# SenseLoRa_Industrial-grade_Air_Monitor_V.net
KiCad netlist of a schematic drawn in EAGLE
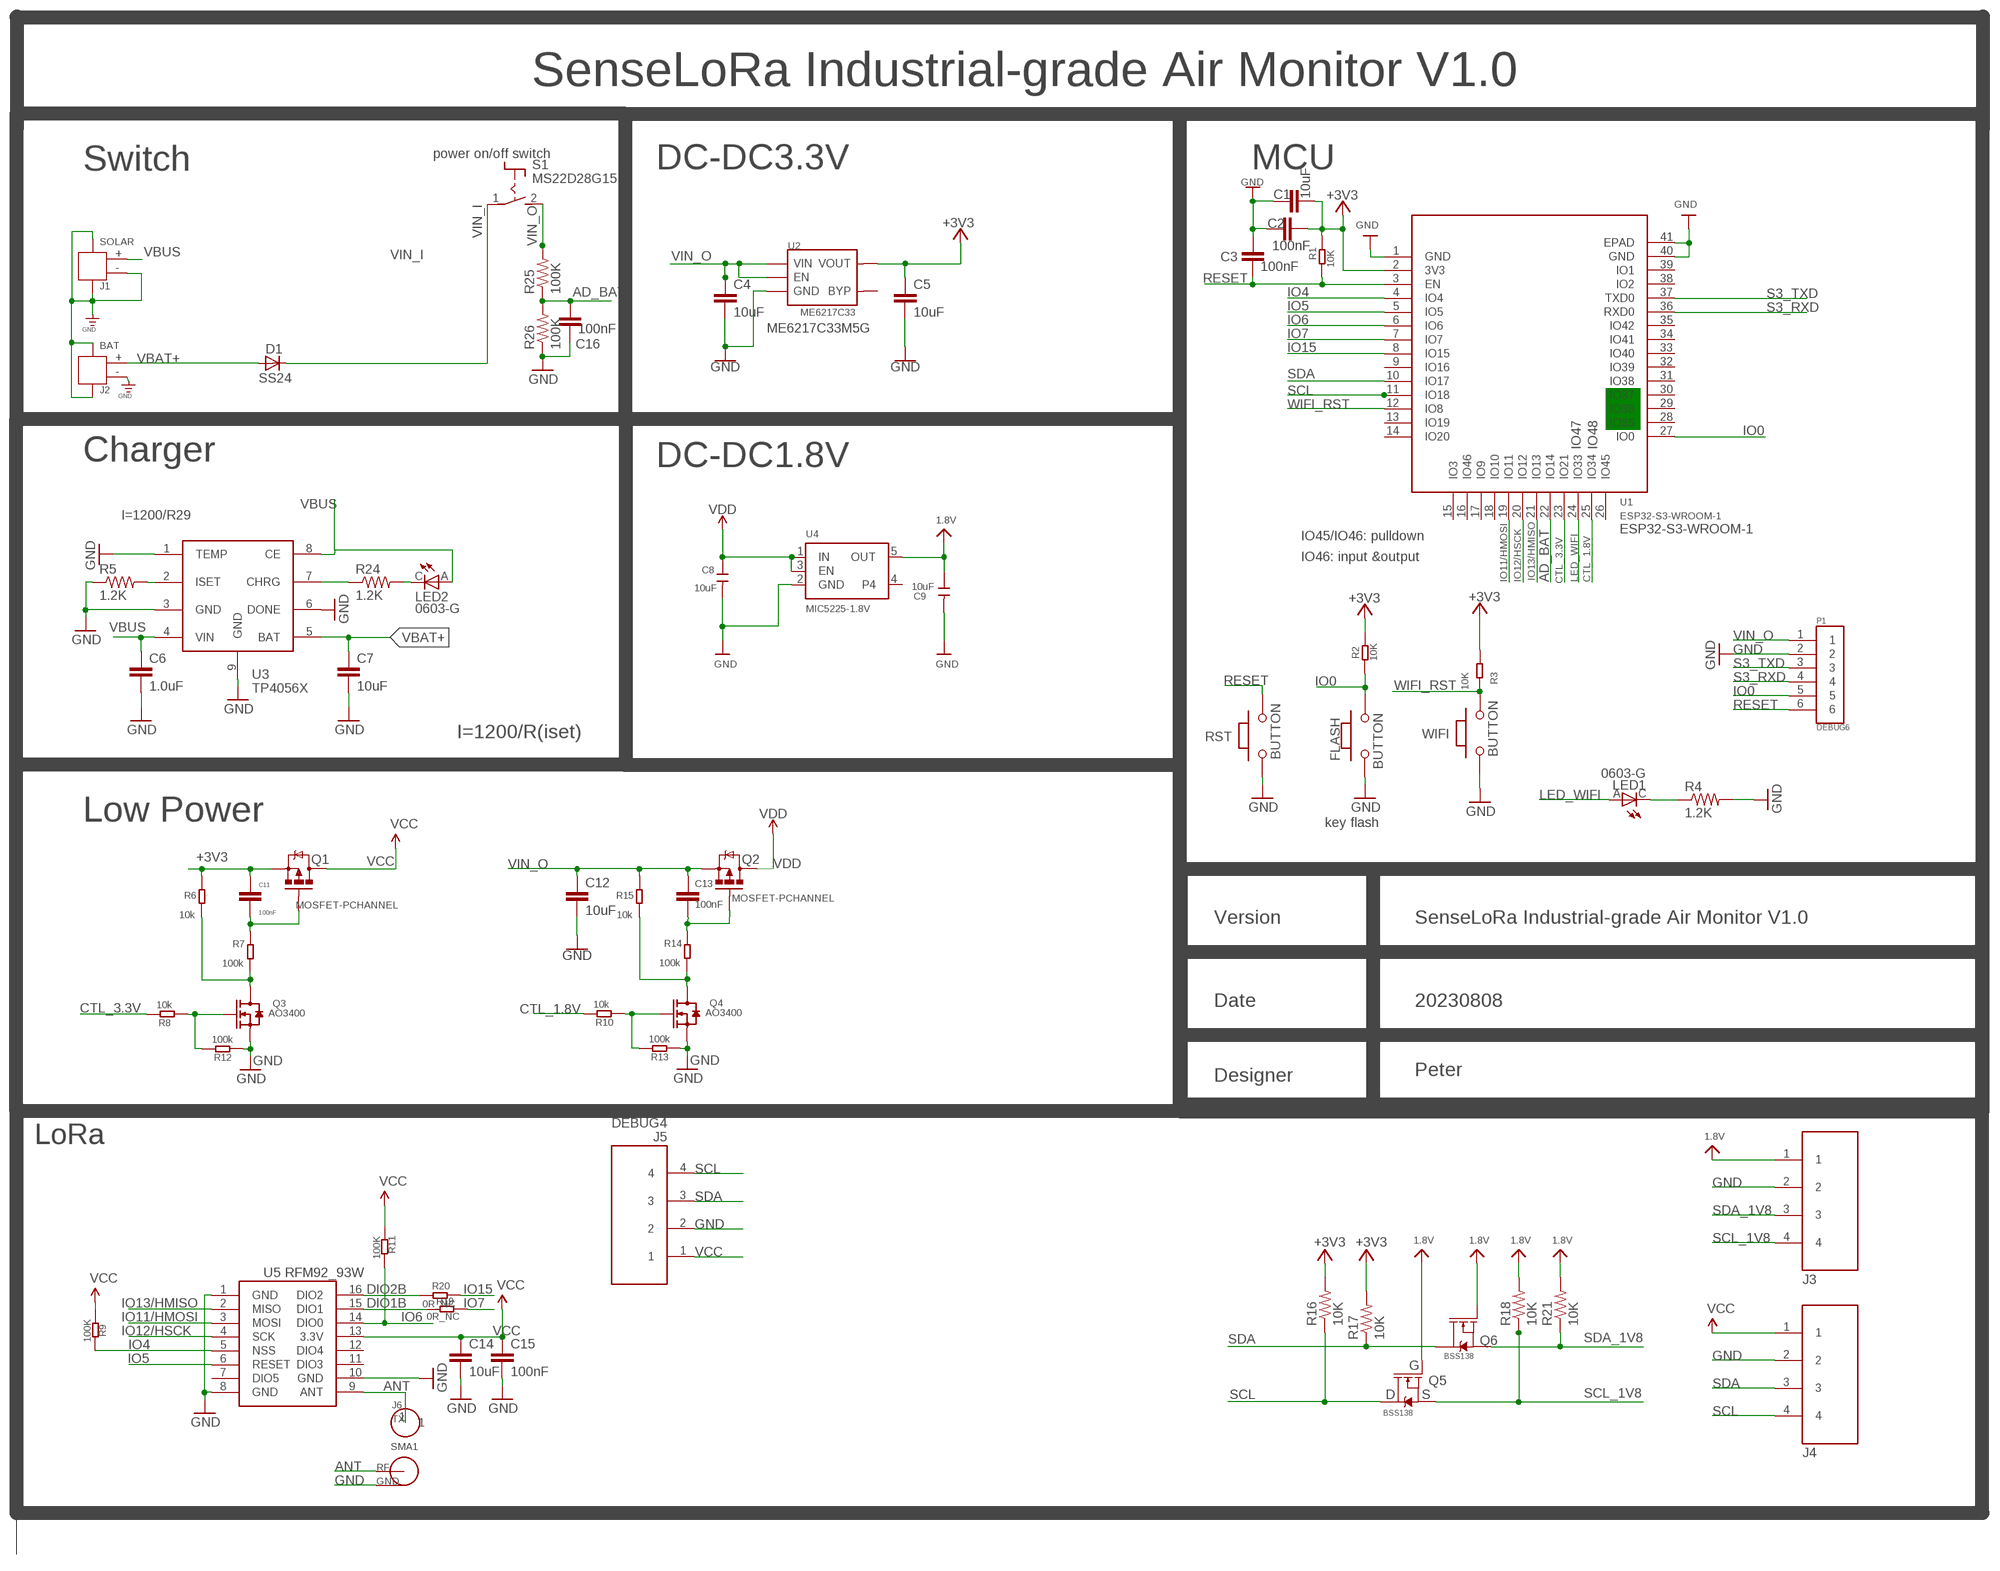
[diagram p0: schematic, sheet 1]

(export (version "E")
  (design (tool "Eeschema 10.0.6"))
  (components
    (comp (ref "C1")
      (value "10uF")
      (footprint "eagle-import:C0603")
      (libsource (lib "eagle-import") (part "C0603"))
    )
    (comp (ref "C2")
      (value "100nF")
      (footprint "eagle-import:C0603")
      (libsource (lib "eagle-import") (part "C0603"))
    )
    (comp (ref "C3")
      (value "100nF")
      (footprint "eagle-import:C0603")
      (libsource (lib "eagle-import") (part "C0603"))
    )
    (comp (ref "C4")
      (value "10uF")
      (footprint "eagle-import:C0603")
      (libsource (lib "eagle-import") (part "C0603"))
    )
    (comp (ref "C5")
      (value "10uF")
      (footprint "eagle-import:C0603")
      (libsource (lib "eagle-import") (part "C0603"))
    )
    (comp (ref "C6")
      (value "1.0uF")
      (footprint "eagle-import:C0603")
      (libsource (lib "eagle-import") (part "C0603"))
    )
    (comp (ref "C7")
      (value "10uF")
      (footprint "eagle-import:C0603")
      (libsource (lib "eagle-import") (part "C0603"))
    )
    (comp (ref "C8")
      (value "10uF")
      (footprint "eagle-import:0603")
      (libsource (lib "eagle-import") (part "C-0603"))
    )
    (comp (ref "C9")
      (value "10uF")
      (footprint "eagle-import:0603")
      (libsource (lib "eagle-import") (part "C-0603"))
    )
    (comp (ref "C11")
      (value "100nF")
      (footprint "eagle-import:C0603")
      (libsource (lib "eagle-import") (part "C0603"))
    )
    (comp (ref "C12")
      (value "10uF")
      (footprint "eagle-import:C0603")
      (libsource (lib "eagle-import") (part "C0603"))
    )
    (comp (ref "C13")
      (value "100nF")
      (footprint "eagle-import:C0603")
      (libsource (lib "eagle-import") (part "C0603"))
    )
    (comp (ref "C14")
      (value "10uF")
      (footprint "eagle-import:C0603")
      (libsource (lib "eagle-import") (part "C0603"))
    )
    (comp (ref "C15")
      (value "100nF")
      (footprint "eagle-import:C0603")
      (libsource (lib "eagle-import") (part "C0603"))
    )
    (comp (ref "C16")
      (value "100nF")
      (footprint "eagle-import:C0603")
      (libsource (lib "eagle-import") (part "C0603"))
    )
    (comp (ref "D1")
      (value "SS24")
      (footprint "eagle-import:DO-214AC")
      (libsource (lib "eagle-import") (part "DIODE-DO-214AC"))
    )
    (comp (ref "FLASH")
      (value "BUTTON")
      (footprint "eagle-import:157SW")
      (libsource (lib "eagle-import") (part "PB157"))
    )
    (comp (ref "J1")
      (value "SOLAR")
      (footprint "eagle-import:HW2-SMD-2.0-90D")
      (libsource (lib "eagle-import") (part "JST-2P-SMD'2.0'"))
    )
    (comp (ref "J2")
      (value "BAT")
      (footprint "eagle-import:HW2-SMD-2.0-90D")
      (libsource (lib "eagle-import") (part "JST-2P-SMD'2.0'"))
    )
    (comp (ref "J3")
      (value "CONNNECT-SMD-1.25X4P")
      (footprint "eagle-import:CONNNECT-SMD-1.25X4P")
      (libsource (lib "eagle-import") (part "CONNNECT-SMD-1.25X4P"))
    )
    (comp (ref "J4")
      (value "CONNNECT-SMD-1.25X4P")
      (footprint "eagle-import:CONNNECT-SMD-1.25X4P")
      (libsource (lib "eagle-import") (part "CONNNECT-SMD-1.25X4P"))
    )
    (comp (ref "J5")
      (value "DEBUG4")
      (footprint "eagle-import:DEBUG_4")
      (libsource (lib "eagle-import") (part "DEBUG4"))
    )
    (comp (ref "J6")
      (value "TX")
      (footprint "eagle-import:1P-100_50MIL")
      (libsource (lib "eagle-import") (part "HEADER-1P-50"))
    )
    (comp (ref "LED1")
      (value "0603-G")
      (footprint "eagle-import:LED0603")
      (libsource (lib "eagle-import") (part "LED0603"))
    )
    (comp (ref "LED2")
      (value "0603-G")
      (footprint "eagle-import:LED0603")
      (libsource (lib "eagle-import") (part "LED0603"))
    )
    (comp (ref "P1")
      (value "DEBUG6")
      (footprint "eagle-import:DEBUG_6")
      (libsource (lib "eagle-import") (part "DEBUG6"))
    )
    (comp (ref "Q1")
      (value "MOSFET-PCHANNEL")
      (footprint "eagle-import:SOT23-3")
      (fields (field (name "PROD_ID") "TRANS-08285"))
      (libsource (lib "eagle-import") (part "MOSFET-PCHANNEL"))
    )
    (comp (ref "Q2")
      (value "MOSFET-PCHANNEL")
      (footprint "eagle-import:SOT23-3")
      (fields (field (name "PROD_ID") "TRANS-08285"))
      (libsource (lib "eagle-import") (part "MOSFET-PCHANNEL"))
    )
    (comp (ref "Q3")
      (value "AO3400")
      (footprint "eagle-import:SOT23@1")
      (libsource (lib "eagle-import") (part "MOSFET-N'SOT23'"))
    )
    (comp (ref "Q4")
      (value "AO3400")
      (footprint "eagle-import:SOT23@1")
      (libsource (lib "eagle-import") (part "MOSFET-N'SOT23'"))
    )
    (comp (ref "Q5")
      (value "BSS138")
      (footprint "eagle-import:SOT23-3")
      (libsource (lib "eagle-import") (part "MOSFET-NCH-BSS138"))
    )
    (comp (ref "Q6")
      (value "BSS138")
      (footprint "eagle-import:SOT23-3")
      (fields (field (name "PROD_ID") "TRANS-00830"))
      (libsource (lib "eagle-import") (part "MOSFET-NCH-BSS138"))
    )
    (comp (ref "R1")
      (value "10K")
      (footprint "eagle-import:R0603")
      (libsource (lib "eagle-import") (part "R-0603"))
    )
    (comp (ref "R2")
      (value "10K")
      (footprint "eagle-import:R0603")
      (libsource (lib "eagle-import") (part "R-0603"))
    )
    (comp (ref "R3")
      (value "10K")
      (footprint "eagle-import:R0603")
      (libsource (lib "eagle-import") (part "R-0603"))
    )
    (comp (ref "R4")
      (value "1.2K")
      (footprint "eagle-import:R0603")
      (libsource (lib "eagle-import") (part "R0603"))
    )
    (comp (ref "R5")
      (value "1.2K")
      (footprint "eagle-import:R0603")
      (libsource (lib "eagle-import") (part "R0603"))
    )
    (comp (ref "R6")
      (value "10k")
      (footprint "eagle-import:R0603")
      (libsource (lib "eagle-import") (part "R-0603"))
    )
    (comp (ref "R7")
      (value "100k")
      (footprint "eagle-import:R0603")
      (libsource (lib "eagle-import") (part "R-0603"))
    )
    (comp (ref "R8")
      (value "10k")
      (footprint "eagle-import:R0603")
      (libsource (lib "eagle-import") (part "R-0603"))
    )
    (comp (ref "R9")
      (value "100K")
      (footprint "eagle-import:R0603")
      (libsource (lib "eagle-import") (part "R-0603"))
    )
    (comp (ref "R10")
      (value "10k")
      (footprint "eagle-import:R0603")
      (libsource (lib "eagle-import") (part "R-0603"))
    )
    (comp (ref "R11")
      (value "100K")
      (footprint "eagle-import:R0603")
      (libsource (lib "eagle-import") (part "R-0603"))
    )
    (comp (ref "R12")
      (value "100k")
      (footprint "eagle-import:R0603")
      (libsource (lib "eagle-import") (part "R-0603"))
    )
    (comp (ref "R13")
      (value "100k")
      (footprint "eagle-import:R0603")
      (libsource (lib "eagle-import") (part "R-0603"))
    )
    (comp (ref "R14")
      (value "100k")
      (footprint "eagle-import:R0603")
      (libsource (lib "eagle-import") (part "R-0603"))
    )
    (comp (ref "R15")
      (value "10k")
      (footprint "eagle-import:R0603")
      (libsource (lib "eagle-import") (part "R-0603"))
    )
    (comp (ref "R16")
      (value "10K")
      (footprint "eagle-import:R0603")
      (libsource (lib "eagle-import") (part "R0603"))
    )
    (comp (ref "R17")
      (value "10K")
      (footprint "eagle-import:R0603")
      (libsource (lib "eagle-import") (part "R0603"))
    )
    (comp (ref "R18")
      (value "10K")
      (footprint "eagle-import:R0603")
      (libsource (lib "eagle-import") (part "R0603"))
    )
    (comp (ref "R19")
      (value "0R_NC")
      (footprint "eagle-import:R0603")
      (libsource (lib "eagle-import") (part "R-0603"))
    )
    (comp (ref "R20")
      (value "0R_NC")
      (footprint "eagle-import:R0603")
      (libsource (lib "eagle-import") (part "R-0603"))
    )
    (comp (ref "R21")
      (value "10K")
      (footprint "eagle-import:R0603")
      (libsource (lib "eagle-import") (part "R0603"))
    )
    (comp (ref "R24")
      (value "1.2K")
      (footprint "eagle-import:R0603")
      (libsource (lib "eagle-import") (part "R0603"))
    )
    (comp (ref "R25")
      (value "100K")
      (footprint "eagle-import:R0603")
      (libsource (lib "eagle-import") (part "R0603"))
    )
    (comp (ref "R26")
      (value "100K")
      (footprint "eagle-import:R0603")
      (libsource (lib "eagle-import") (part "R0603"))
    )
    (comp (ref "RST")
      (value "BUTTON")
      (footprint "eagle-import:157SW")
      (libsource (lib "eagle-import") (part "PB157"))
    )
    (comp (ref "S1")
      (value "MS22D28G15")
      (footprint "eagle-import:S-MS22D28G15")
      (libsource (lib "eagle-import") (part "MS22D28G15"))
    )
    (comp (ref "SMA1")
      (value "SMA-KWE")
      (footprint "eagle-import:SMA-KWE")
      (libsource (lib "eagle-import") (part "SMA-KWE"))
    )
    (comp (ref "U1")
      (value "ESP32-S3-WROOM-1")
      (footprint "eagle-import:ESP32-­S2-­SOLO")
      (libsource (lib "eagle-import") (part "ESP32­S2­SOLO"))
    )
    (comp (ref "U2")
      (value "ME6217C33")
      (footprint "eagle-import:SOT23-5")
      (libsource (lib "eagle-import") (part "SPX3819"))
    )
    (comp (ref "U3")
      (value "TP4056X")
      (footprint "eagle-import:SOP8-1.27P")
      (libsource (lib "eagle-import") (part "TP4056"))
    )
    (comp (ref "U4")
      (value "MIC5225-1.8V")
      (footprint "eagle-import:SOT23-5")
      (libsource (lib "eagle-import") (part "VREG_SOT23-5"))
    )
    (comp (ref "U5")
      (value "RFM92_93W")
      (footprint "eagle-import:RFM92_93W")
      (libsource (lib "eagle-import") (part "RFM92_93W"))
    )
    (comp (ref "WIFI")
      (value "BUTTON")
      (footprint "eagle-import:157SW")
      (libsource (lib "eagle-import") (part "PB157"))
    )
  )
  (nets
    (net (code "1") (name "+3V3") (class "Default")
      (node (ref "C1") (pin "2") (pinfunction "2_2") (pintype "passive"))
      (node (ref "C11") (pin "1") (pinfunction "1_1") (pintype "passive"))
      (node (ref "C2") (pin "2") (pinfunction "2_2") (pintype "passive"))
      (node (ref "C5") (pin "1") (pinfunction "1_1") (pintype "passive"))
      (node (ref "Q1") (pin "2") (pinfunction "S_2") (pintype "passive"))
      (node (ref "R1") (pin "2") (pinfunction "2_2") (pintype "passive"))
      (node (ref "R16") (pin "2") (pinfunction "2_2") (pintype "passive"))
      (node (ref "R17") (pin "2") (pinfunction "2_2") (pintype "passive"))
      (node (ref "R2") (pin "2") (pinfunction "2_2") (pintype "passive"))
      (node (ref "R3") (pin "2") (pinfunction "2_2") (pintype "passive"))
      (node (ref "R6") (pin "2") (pinfunction "2_2") (pintype "passive"))
      (node (ref "U1") (pin "2") (pinfunction "3V3_2") (pintype "bidirectional"))
      (node (ref "U2") (pin "5") (pinfunction "VOUT_5") (pintype "bidirectional"))
    )
    (net (code "2") (name "/AD_BAT") (class "Default")
      (node (ref "C16") (pin "2") (pinfunction "2_2") (pintype "passive"))
      (node (ref "R25") (pin "1") (pinfunction "1_1") (pintype "passive"))
      (node (ref "R26") (pin "2") (pinfunction "2_2") (pintype "passive"))
      (node (ref "U1") (pin "22") (pinfunction "IO14_22") (pintype "bidirectional"))
    )
    (net (code "3") (name "/ANT") (class "Default")
      (node (ref "J6") (pin "1") (pinfunction "1_1") (pintype "bidirectional"))
      (node (ref "SMA1") (pin "1") (pinfunction "SIG_1") (pintype "passive"))
      (node (ref "U5") (pin "9") (pinfunction "ANT_9") (pintype "bidirectional"))
    )
    (net (code "4") (name "/CTL_1.8V") (class "Default")
      (node (ref "R10") (pin "2") (pinfunction "2_2") (pintype "passive"))
      (node (ref "U1") (pin "25") (pinfunction "IO34_25") (pintype "bidirectional"))
    )
    (net (code "5") (name "/CTL_3.3V") (class "Default")
      (node (ref "R8") (pin "2") (pinfunction "2_2") (pintype "passive"))
      (node (ref "U1") (pin "23") (pinfunction "IO21_23") (pintype "bidirectional"))
    )
    (net (code "6") (name "/DIO1B") (class "Default")
      (node (ref "R19") (pin "2") (pinfunction "2_2") (pintype "passive"))
      (node (ref "U5") (pin "15") (pinfunction "DIO1_15") (pintype "bidirectional"))
    )
    (net (code "7") (name "/DIO2B") (class "Default")
      (node (ref "R20") (pin "2") (pinfunction "2_2") (pintype "passive"))
      (node (ref "U5") (pin "16") (pinfunction "DIO2_16") (pintype "bidirectional"))
    )
    (net (code "8") (name "/IO0") (class "Default")
      (node (ref "FLASH") (pin "2") (pinfunction "2_2") (pintype "passive"))
      (node (ref "P1") (pin "5") (pinfunction "5_5") (pintype "bidirectional"))
      (node (ref "R2") (pin "1") (pinfunction "1_1") (pintype "passive"))
      (node (ref "U1") (pin "27") (pinfunction "IO0_27") (pintype "bidirectional"))
    )
    (net (code "9") (name "/IO4") (class "Default")
      (node (ref "R9") (pin "1") (pinfunction "1_1") (pintype "passive"))
      (node (ref "U1") (pin "4") (pinfunction "IO4_4") (pintype "bidirectional"))
      (node (ref "U5") (pin "5") (pinfunction "NSS_5") (pintype "bidirectional"))
    )
    (net (code "10") (name "/IO5") (class "Default")
      (node (ref "U1") (pin "5") (pinfunction "IO5_5") (pintype "bidirectional"))
      (node (ref "U5") (pin "6") (pinfunction "RESET_6") (pintype "bidirectional"))
    )
    (net (code "11") (name "/IO6") (class "Default")
      (node (ref "R11") (pin "1") (pinfunction "1_1") (pintype "passive"))
      (node (ref "U1") (pin "6") (pinfunction "IO6_6") (pintype "bidirectional"))
      (node (ref "U5") (pin "14") (pinfunction "DIO0_14") (pintype "bidirectional"))
    )
    (net (code "12") (name "/IO7") (class "Default")
      (node (ref "R19") (pin "1") (pinfunction "1_1") (pintype "passive"))
      (node (ref "U1") (pin "7") (pinfunction "IO7_7") (pintype "bidirectional"))
    )
    (net (code "13") (name "/IO11{slash}HMOSI") (class "Default")
      (node (ref "U1") (pin "19") (pinfunction "IO11_19") (pintype "bidirectional"))
      (node (ref "U5") (pin "3") (pinfunction "MOSI_3") (pintype "bidirectional"))
    )
    (net (code "14") (name "/IO12{slash}HSCK") (class "Default")
      (node (ref "U1") (pin "20") (pinfunction "IO12_20") (pintype "bidirectional"))
      (node (ref "U5") (pin "4") (pinfunction "SCK_4") (pintype "bidirectional"))
    )
    (net (code "15") (name "/IO13{slash}HMISO") (class "Default")
      (node (ref "U1") (pin "21") (pinfunction "IO13_21") (pintype "bidirectional"))
      (node (ref "U5") (pin "2") (pinfunction "MISO_2") (pintype "bidirectional"))
    )
    (net (code "16") (name "/IO15") (class "Default")
      (node (ref "R20") (pin "1") (pinfunction "1_1") (pintype "passive"))
      (node (ref "U1") (pin "8") (pinfunction "IO15_8") (pintype "bidirectional"))
    )
    (net (code "17") (name "/LED_WIFI") (class "Default")
      (node (ref "LED1") (pin "A") (pinfunction "A_A") (pintype "passive"))
      (node (ref "U1") (pin "24") (pinfunction "IO33_24") (pintype "bidirectional"))
    )
    (net (code "18") (name "/RESET") (class "Default")
      (node (ref "C3") (pin "1") (pinfunction "1_1") (pintype "passive"))
      (node (ref "P1") (pin "6") (pinfunction "6_6") (pintype "bidirectional"))
      (node (ref "R1") (pin "1") (pinfunction "1_1") (pintype "passive"))
      (node (ref "RST") (pin "2") (pinfunction "2_2") (pintype "passive"))
      (node (ref "U1") (pin "3") (pinfunction "EN_3") (pintype "bidirectional"))
    )
    (net (code "19") (name "/S3_RXD") (class "Default")
      (node (ref "P1") (pin "4") (pinfunction "4_4") (pintype "bidirectional"))
      (node (ref "U1") (pin "36") (pinfunction "RXD0_36") (pintype "bidirectional"))
    )
    (net (code "20") (name "/S3_TXD") (class "Default")
      (node (ref "P1") (pin "3") (pinfunction "3_3") (pintype "bidirectional"))
      (node (ref "U1") (pin "37") (pinfunction "TXD0_37") (pintype "bidirectional"))
    )
    (net (code "21") (name "/SCL") (class "Default")
      (node (ref "J4") (pin "4") (pinfunction "4_4") (pintype "bidirectional"))
      (node (ref "J5") (pin "4") (pinfunction "4_4") (pintype "bidirectional"))
      (node (ref "Q5") (pin "3") (pinfunction "D_3") (pintype "bidirectional"))
      (node (ref "R16") (pin "1") (pinfunction "1_1") (pintype "passive"))
      (node (ref "U1") (pin "11") (pinfunction "IO18_11") (pintype "bidirectional"))
    )
    (net (code "22") (name "/SCL_1V8") (class "Default")
      (node (ref "J3") (pin "4") (pinfunction "4_4") (pintype "bidirectional"))
      (node (ref "Q5") (pin "2") (pinfunction "S_2") (pintype "bidirectional"))
      (node (ref "R18") (pin "1") (pinfunction "1_1") (pintype "passive"))
    )
    (net (code "23") (name "/SDA") (class "Default")
      (node (ref "J4") (pin "3") (pinfunction "3_3") (pintype "bidirectional"))
      (node (ref "J5") (pin "3") (pinfunction "3_3") (pintype "bidirectional"))
      (node (ref "Q6") (pin "3") (pinfunction "D_3") (pintype "bidirectional"))
      (node (ref "R17") (pin "1") (pinfunction "1_1") (pintype "passive"))
      (node (ref "U1") (pin "10") (pinfunction "IO17_10") (pintype "bidirectional"))
    )
    (net (code "24") (name "/SDA_1V8") (class "Default")
      (node (ref "J3") (pin "3") (pinfunction "3_3") (pintype "bidirectional"))
      (node (ref "Q6") (pin "2") (pinfunction "S_2") (pintype "bidirectional"))
      (node (ref "R21") (pin "1") (pinfunction "1_1") (pintype "passive"))
    )
    (net (code "25") (name "/VBUS") (class "Default")
      (node (ref "C6") (pin "1") (pinfunction "1_1") (pintype "passive"))
      (node (ref "J1") (pin "+") (pinfunction "1_+") (pintype "bidirectional"))
      (node (ref "LED2") (pin "A") (pinfunction "A_A") (pintype "passive"))
      (node (ref "U3") (pin "4") (pinfunction "VIN_4") (pintype "bidirectional"))
      (node (ref "U3") (pin "8") (pinfunction "CE_8") (pintype "bidirectional"))
    )
    (net (code "26") (name "/VIN_I") (class "Default")
      (node (ref "D1") (pin "C") (pinfunction "C_C") (pintype "passive"))
      (node (ref "S1") (pin "1") (pinfunction "P_1") (pintype "passive"))
    )
    (net (code "27") (name "/VIN_O") (class "Default")
      (node (ref "C12") (pin "1") (pinfunction "1_1") (pintype "passive"))
      (node (ref "C13") (pin "1") (pinfunction "1_1") (pintype "passive"))
      (node (ref "C4") (pin "1") (pinfunction "1_1") (pintype "passive"))
      (node (ref "P1") (pin "1") (pinfunction "1_1") (pintype "bidirectional"))
      (node (ref "Q2") (pin "2") (pinfunction "S_2") (pintype "passive"))
      (node (ref "R15") (pin "2") (pinfunction "2_2") (pintype "passive"))
      (node (ref "R25") (pin "2") (pinfunction "2_2") (pintype "passive"))
      (node (ref "S1") (pin "2") (pinfunction "S_2") (pintype "passive"))
      (node (ref "U2") (pin "1") (pinfunction "VIN_1") (pintype "bidirectional"))
      (node (ref "U2") (pin "3") (pinfunction "EN_3") (pintype "bidirectional"))
    )
    (net (code "28") (name "/WIFI_RST") (class "Default")
      (node (ref "R3") (pin "1") (pinfunction "1_1") (pintype "passive"))
      (node (ref "U1") (pin "12") (pinfunction "IO8_12") (pintype "bidirectional"))
      (node (ref "WIFI") (pin "2") (pinfunction "2_2") (pintype "passive"))
    )
    (net (code "29") (name "1.8V") (class "Default")
      (node (ref "C9") (pin "1") (pinfunction "1_1") (pintype "passive"))
      (node (ref "J3") (pin "1") (pinfunction "1_1") (pintype "bidirectional"))
      (node (ref "Q5") (pin "1") (pinfunction "G_1") (pintype "bidirectional"))
      (node (ref "Q6") (pin "1") (pinfunction "G_1") (pintype "bidirectional"))
      (node (ref "R18") (pin "2") (pinfunction "2_2") (pintype "passive"))
      (node (ref "R21") (pin "2") (pinfunction "2_2") (pintype "passive"))
      (node (ref "U4") (pin "5") (pinfunction "OUT_5") (pintype "power_in"))
    )
    (net (code "30") (name "GND") (class "Default")
      (node (ref "C1") (pin "1") (pinfunction "1_1") (pintype "passive"))
      (node (ref "C12") (pin "2") (pinfunction "2_2") (pintype "passive"))
      (node (ref "C14") (pin "2") (pinfunction "2_2") (pintype "passive"))
      (node (ref "C15") (pin "2") (pinfunction "2_2") (pintype "passive"))
      (node (ref "C16") (pin "1") (pinfunction "1_1") (pintype "passive"))
      (node (ref "C2") (pin "1") (pinfunction "1_1") (pintype "passive"))
      (node (ref "C3") (pin "2") (pinfunction "2_2") (pintype "passive"))
      (node (ref "C4") (pin "2") (pinfunction "2_2") (pintype "passive"))
      (node (ref "C5") (pin "2") (pinfunction "2_2") (pintype "passive"))
      (node (ref "C6") (pin "2") (pinfunction "2_2") (pintype "passive"))
      (node (ref "C7") (pin "2") (pinfunction "2_2") (pintype "passive"))
      (node (ref "C8") (pin "2") (pinfunction "2_2") (pintype "passive"))
      (node (ref "C9") (pin "2") (pinfunction "2_2") (pintype "passive"))
      (node (ref "FLASH") (pin "1") (pinfunction "1_1") (pintype "passive"))
      (node (ref "J1") (pin "-") (pinfunction "2_-") (pintype "bidirectional"))
      (node (ref "J1") (pin "3") (pinfunction "3_3") (pintype "bidirectional"))
      (node (ref "J1") (pin "4") (pinfunction "4_4") (pintype "bidirectional"))
      (node (ref "J2") (pin "-") (pinfunction "2_-") (pintype "bidirectional"))
      (node (ref "J2") (pin "3") (pinfunction "3_3") (pintype "bidirectional"))
      (node (ref "J2") (pin "4") (pinfunction "4_4") (pintype "bidirectional"))
      (node (ref "J3") (pin "2") (pinfunction "2_2") (pintype "bidirectional"))
      (node (ref "J4") (pin "2") (pinfunction "2_2") (pintype "bidirectional"))
      (node (ref "J5") (pin "2") (pinfunction "2_2") (pintype "bidirectional"))
      (node (ref "P1") (pin "2") (pinfunction "2_2") (pintype "bidirectional"))
      (node (ref "Q3") (pin "2") (pinfunction "S_2") (pintype "passive"))
      (node (ref "Q4") (pin "2") (pinfunction "S_2") (pintype "passive"))
      (node (ref "R12") (pin "1") (pinfunction "1_1") (pintype "passive"))
      (node (ref "R13") (pin "1") (pinfunction "1_1") (pintype "passive"))
      (node (ref "R26") (pin "1") (pinfunction "1_1") (pintype "passive"))
      (node (ref "R4") (pin "2") (pinfunction "2_2") (pintype "passive"))
      (node (ref "R5") (pin "1") (pinfunction "1_1") (pintype "passive"))
      (node (ref "RST") (pin "1") (pinfunction "1_1") (pintype "passive"))
      (node (ref "SMA1") (pin "2") (pinfunction "GND_2") (pintype "passive"))
      (node (ref "SMA1") (pin "3") (pinfunction "GND_3") (pintype "passive"))
      (node (ref "SMA1") (pin "4") (pinfunction "GND_4") (pintype "passive"))
      (node (ref "SMA1") (pin "5") (pinfunction "GND_5") (pintype "passive"))
      (node (ref "U1") (pin "1") (pinfunction "GND_1") (pintype "bidirectional"))
      (node (ref "U1") (pin "40") (pinfunction "GND_40") (pintype "bidirectional"))
      (node (ref "U1") (pin "41") (pinfunction "EPAD_41") (pintype "bidirectional"))
      (node (ref "U2") (pin "2") (pinfunction "GND_2") (pintype "bidirectional"))
      (node (ref "U3") (pin "1") (pinfunction "TEMP_1") (pintype "bidirectional"))
      (node (ref "U3") (pin "3") (pinfunction "GND_3") (pintype "bidirectional"))
      (node (ref "U3") (pin "6") (pinfunction "DONE_6") (pintype "bidirectional"))
      (node (ref "U3") (pin "9") (pinfunction "GND_9") (pintype "bidirectional"))
      (node (ref "U4") (pin "2") (pinfunction "GND_2") (pintype "power_in"))
      (node (ref "U5") (pin "1") (pinfunction "GND_1") (pintype "power_in"))
      (node (ref "U5") (pin "10") (pinfunction "GND_10") (pintype "power_in"))
      (node (ref "U5") (pin "8") (pinfunction "GND_8") (pintype "power_in"))
      (node (ref "WIFI") (pin "1") (pinfunction "1_1") (pintype "passive"))
    )
    (net (code "31") (name "Net-(LED1-PadC)") (class "Default")
      (node (ref "LED1") (pin "C") (pinfunction "C_C") (pintype "passive"))
      (node (ref "R4") (pin "1") (pinfunction "1_1") (pintype "passive"))
    )
    (net (code "32") (name "Net-(LED2-PadC)") (class "Default")
      (node (ref "LED2") (pin "C") (pinfunction "C_C") (pintype "passive"))
      (node (ref "R24") (pin "2") (pinfunction "2_2") (pintype "passive"))
    )
    (net (code "33") (name "Net-(Q1-G)") (class "Default")
      (node (ref "C11") (pin "2") (pinfunction "2_2") (pintype "passive"))
      (node (ref "Q1") (pin "1") (pinfunction "G_1") (pintype "passive"))
      (node (ref "R7") (pin "2") (pinfunction "2_2") (pintype "passive"))
    )
    (net (code "34") (name "Net-(Q2-G)") (class "Default")
      (node (ref "C13") (pin "2") (pinfunction "2_2") (pintype "passive"))
      (node (ref "Q2") (pin "1") (pinfunction "G_1") (pintype "passive"))
      (node (ref "R14") (pin "2") (pinfunction "2_2") (pintype "passive"))
    )
    (net (code "35") (name "Net-(Q3-D)") (class "Default")
      (node (ref "Q3") (pin "3") (pinfunction "D_3") (pintype "passive"))
      (node (ref "R6") (pin "1") (pinfunction "1_1") (pintype "passive"))
      (node (ref "R7") (pin "1") (pinfunction "1_1") (pintype "passive"))
    )
    (net (code "36") (name "Net-(Q3-G)") (class "Default")
      (node (ref "Q3") (pin "1") (pinfunction "G_1") (pintype "passive"))
      (node (ref "R12") (pin "2") (pinfunction "2_2") (pintype "passive"))
      (node (ref "R8") (pin "1") (pinfunction "1_1") (pintype "passive"))
    )
    (net (code "37") (name "Net-(Q4-D)") (class "Default")
      (node (ref "Q4") (pin "3") (pinfunction "D_3") (pintype "passive"))
      (node (ref "R14") (pin "1") (pinfunction "1_1") (pintype "passive"))
      (node (ref "R15") (pin "1") (pinfunction "1_1") (pintype "passive"))
    )
    (net (code "38") (name "Net-(Q4-G)") (class "Default")
      (node (ref "Q4") (pin "1") (pinfunction "G_1") (pintype "passive"))
      (node (ref "R10") (pin "1") (pinfunction "1_1") (pintype "passive"))
      (node (ref "R13") (pin "2") (pinfunction "2_2") (pintype "passive"))
    )
    (net (code "39") (name "Net-(U3-CHRG)") (class "Default")
      (node (ref "R24") (pin "1") (pinfunction "1_1") (pintype "passive"))
      (node (ref "U3") (pin "7") (pinfunction "CHRG_7") (pintype "bidirectional"))
    )
    (net (code "40") (name "Net-(U3-ISET)") (class "Default")
      (node (ref "R5") (pin "2") (pinfunction "2_2") (pintype "passive"))
      (node (ref "U3") (pin "2") (pinfunction "ISET_2") (pintype "bidirectional"))
    )
    (net (code "41") (name "VBAT+") (class "Default")
      (node (ref "C7") (pin "1") (pinfunction "1_1") (pintype "passive"))
      (node (ref "D1") (pin "A") (pinfunction "A_A") (pintype "passive"))
      (node (ref "J2") (pin "+") (pinfunction "1_+") (pintype "bidirectional"))
      (node (ref "U3") (pin "5") (pinfunction "BAT_5") (pintype "bidirectional"))
    )
    (net (code "42") (name "VCC") (class "Default")
      (node (ref "C14") (pin "1") (pinfunction "1_1") (pintype "passive"))
      (node (ref "C15") (pin "1") (pinfunction "1_1") (pintype "passive"))
      (node (ref "J4") (pin "1") (pinfunction "1_1") (pintype "bidirectional"))
      (node (ref "J5") (pin "1") (pinfunction "1_1") (pintype "bidirectional"))
      (node (ref "Q1") (pin "3") (pinfunction "D_3") (pintype "passive"))
      (node (ref "R11") (pin "2") (pinfunction "2_2") (pintype "passive"))
      (node (ref "R9") (pin "2") (pinfunction "2_2") (pintype "passive"))
      (node (ref "U5") (pin "13") (pinfunction "3.3V_13") (pintype "power_in"))
    )
    (net (code "43") (name "VDD") (class "Default")
      (node (ref "C8") (pin "1") (pinfunction "1_1") (pintype "passive"))
      (node (ref "Q2") (pin "3") (pinfunction "D_3") (pintype "passive"))
      (node (ref "U4") (pin "1") (pinfunction "IN_1") (pintype "power_in"))
      (node (ref "U4") (pin "3") (pinfunction "EN_3") (pintype "input"))
    )
    (net (code "44") (name "unconnected-(U1-IO1-Pad39)") (class "Default")
      (node (ref "U1") (pin "39") (pinfunction "IO1_39") (pintype "bidirectional"))
    )
    (net (code "45") (name "unconnected-(U1-IO2-Pad38)") (class "Default")
      (node (ref "U1") (pin "38") (pinfunction "IO2_38") (pintype "bidirectional"))
    )
    (net (code "46") (name "unconnected-(U1-IO3-Pad15)") (class "Default")
      (node (ref "U1") (pin "15") (pinfunction "IO3_15") (pintype "bidirectional"))
    )
    (net (code "47") (name "unconnected-(U1-IO9-Pad17)") (class "Default")
      (node (ref "U1") (pin "17") (pinfunction "IO9_17") (pintype "bidirectional"))
    )
    (net (code "48") (name "unconnected-(U1-IO10-Pad18)") (class "Default")
      (node (ref "U1") (pin "18") (pinfunction "IO10_18") (pintype "bidirectional"))
    )
    (net (code "49") (name "unconnected-(U1-IO16-Pad9)") (class "Default")
      (node (ref "U1") (pin "9") (pinfunction "IO16_9") (pintype "bidirectional"))
    )
    (net (code "50") (name "unconnected-(U1-IO19-Pad13)") (class "Default")
      (node (ref "U1") (pin "13") (pinfunction "IO19_13") (pintype "bidirectional"))
    )
    (net (code "51") (name "unconnected-(U1-IO20-Pad14)") (class "Default")
      (node (ref "U1") (pin "14") (pinfunction "IO20_14") (pintype "bidirectional"))
    )
    (net (code "52") (name "unconnected-(U1-IO35-Pad28)") (class "Default")
      (node (ref "U1") (pin "28") (pinfunction "IO35_28") (pintype "bidirectional"))
    )
    (net (code "53") (name "unconnected-(U1-IO36-Pad29)") (class "Default")
      (node (ref "U1") (pin "29") (pinfunction "IO36_29") (pintype "bidirectional"))
    )
    (net (code "54") (name "unconnected-(U1-IO37-Pad30)") (class "Default")
      (node (ref "U1") (pin "30") (pinfunction "IO37_30") (pintype "bidirectional"))
    )
    (net (code "55") (name "unconnected-(U1-IO38-Pad31)") (class "Default")
      (node (ref "U1") (pin "31") (pinfunction "IO38_31") (pintype "bidirectional"))
    )
    (net (code "56") (name "unconnected-(U1-IO39-Pad32)") (class "Default")
      (node (ref "U1") (pin "32") (pinfunction "IO39_32") (pintype "bidirectional"))
    )
    (net (code "57") (name "unconnected-(U1-IO40-Pad33)") (class "Default")
      (node (ref "U1") (pin "33") (pinfunction "IO40_33") (pintype "bidirectional"))
    )
    (net (code "58") (name "unconnected-(U1-IO41-Pad34)") (class "Default")
      (node (ref "U1") (pin "34") (pinfunction "IO41_34") (pintype "bidirectional"))
    )
    (net (code "59") (name "unconnected-(U1-IO42-Pad35)") (class "Default")
      (node (ref "U1") (pin "35") (pinfunction "IO42_35") (pintype "bidirectional"))
    )
    (net (code "60") (name "unconnected-(U1-IO45-Pad26)") (class "Default")
      (node (ref "U1") (pin "26") (pinfunction "IO45_26") (pintype "bidirectional"))
    )
    (net (code "61") (name "unconnected-(U1-IO46-Pad16)") (class "Default")
      (node (ref "U1") (pin "16") (pinfunction "IO46_16") (pintype "bidirectional"))
    )
    (net (code "62") (name "unconnected-(U2-BYP-Pad4)") (class "Default")
      (node (ref "U2") (pin "4") (pinfunction "BYP_4") (pintype "bidirectional"))
    )
    (net (code "63") (name "unconnected-(U4-P4-Pad4)") (class "Default")
      (node (ref "U4") (pin "4") (pinfunction "P4_4") (pintype "bidirectional"))
    )
    (net (code "64") (name "unconnected-(U5-DIO3-Pad11)") (class "Default")
      (node (ref "U5") (pin "11") (pinfunction "DIO3_11") (pintype "bidirectional"))
    )
    (net (code "65") (name "unconnected-(U5-DIO4-Pad12)") (class "Default")
      (node (ref "U5") (pin "12") (pinfunction "DIO4_12") (pintype "bidirectional"))
    )
    (net (code "66") (name "unconnected-(U5-DIO5-Pad7)") (class "Default")
      (node (ref "U5") (pin "7") (pinfunction "DIO5_7") (pintype "bidirectional"))
    )
  )
)
